# AdapterBoard.net
KiCad netlist of a schematic drawn in Altium Designer
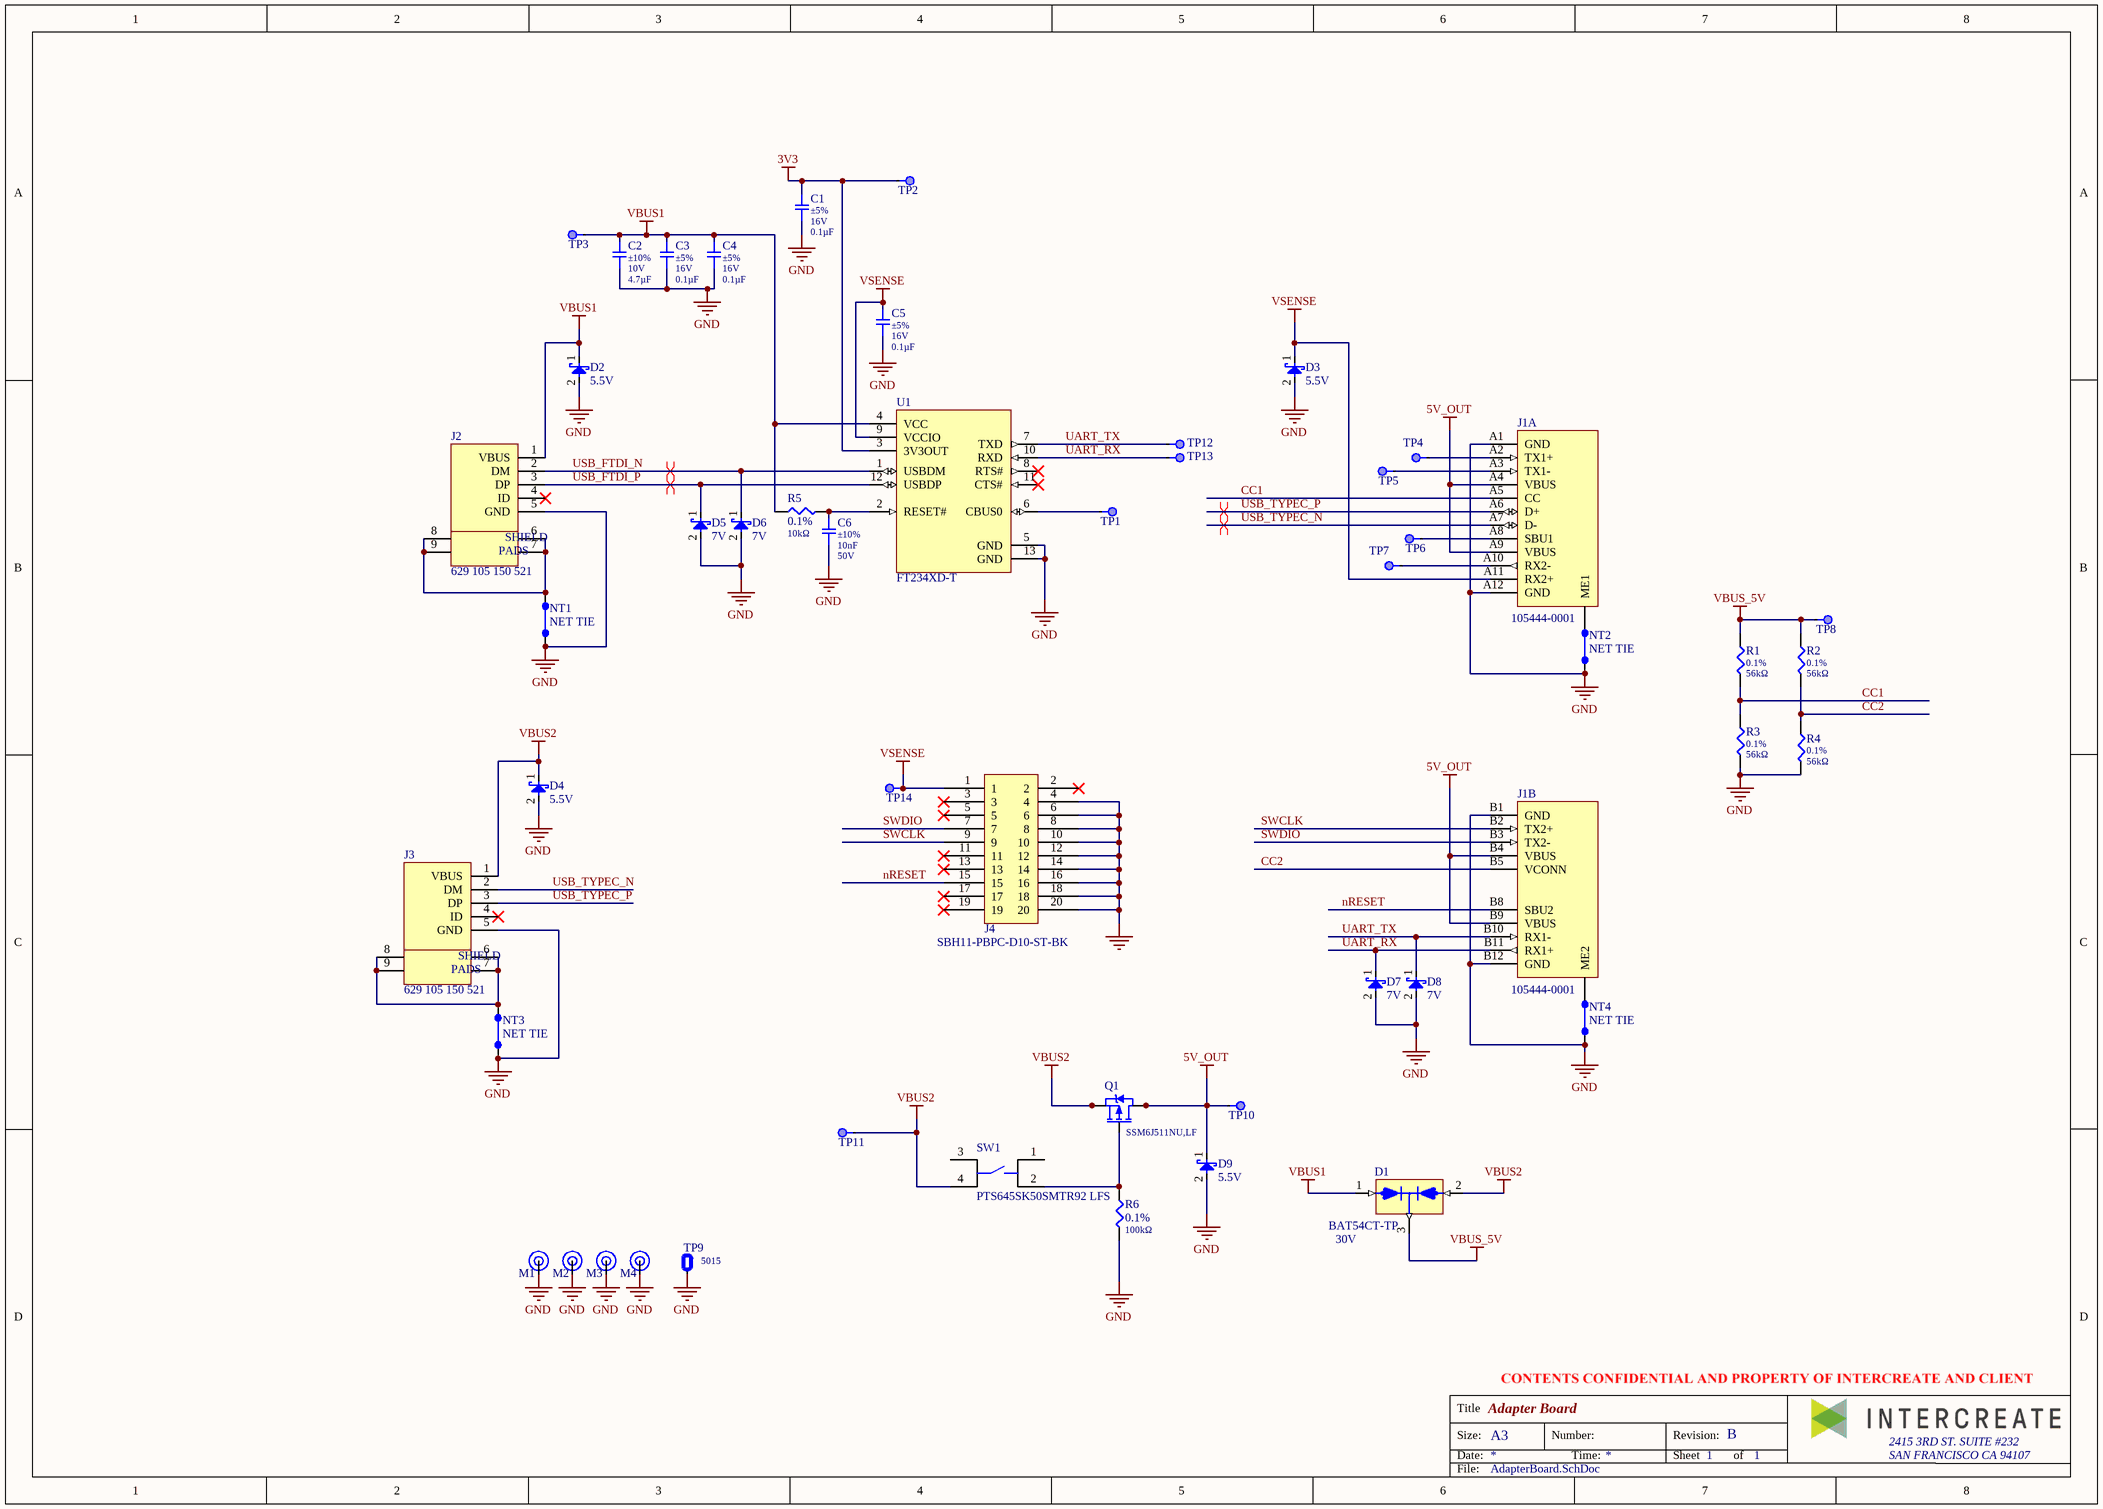
[diagram p0: AdapterBoard.SchDoc]

(export (version "E")
  (design (tool "Eeschema 10.0.6"))
  (components
    (comp (ref "C1")
      (value "0.1µF")
      (footprint "CAP-0402")
      (description "CAP CER 0.1UF 16V X7R 0402 5%")
      (fields
        (field (name "MANUFACTURER") "Murata")
        (field (name "MPN") "GRM155R71C104JA88D")
        (field (name "TOLERANCE") "±5%")
        (field (name "VOLTAGE RATING") "16V")
      )
      (libsource (lib "kagwerks") (part "CAP-0.1uF-16V-0402"))
    )
    (comp (ref "C2")
      (value "4.7µF")
      (footprint "CAP-0402")
      (description "CAP CER 4.7UF 10V X5R 0402 10%")
      (fields
        (field (name "MANUFACTURER") "Samsung")
        (field (name "MPN") "CL05A475KP5NRNC")
        (field (name "TOLERANCE") "±10%")
        (field (name "VOLTAGE RATING") "10V")
      )
      (libsource (lib "kagwerks") (part "CAP-4.7uF-10V-0402"))
    )
    (comp (ref "C3")
      (value "0.1µF")
      (footprint "CAP-0402")
      (description "CAP CER 0.1UF 16V X7R 0402 5%")
      (fields
        (field (name "MANUFACTURER") "Murata")
        (field (name "MPN") "GRM155R71C104JA88D")
        (field (name "TOLERANCE") "±5%")
        (field (name "VOLTAGE RATING") "16V")
      )
      (libsource (lib "kagwerks") (part "CAP-0.1uF-16V-0402"))
    )
    (comp (ref "C4")
      (value "0.1µF")
      (footprint "CAP-0402")
      (description "CAP CER 0.1UF 16V X7R 0402 5%")
      (fields
        (field (name "MANUFACTURER") "Murata")
        (field (name "MPN") "GRM155R71C104JA88D")
        (field (name "TOLERANCE") "±5%")
        (field (name "VOLTAGE RATING") "16V")
      )
      (libsource (lib "kagwerks") (part "CAP-0.1uF-16V-0402"))
    )
    (comp (ref "C5")
      (value "0.1µF")
      (footprint "CAP-0402")
      (description "CAP CER 0.1UF 16V X7R 0402 5%")
      (fields
        (field (name "MANUFACTURER") "Murata")
        (field (name "MPN") "GRM155R71C104JA88D")
        (field (name "TOLERANCE") "±5%")
        (field (name "VOLTAGE RATING") "16V")
      )
      (libsource (lib "kagwerks") (part "CAP-0.1uF-16V-0402"))
    )
    (comp (ref "C6")
      (value "10nF")
      (footprint "CAP-0402")
      (description "CAP CER 10nF 50V X7R 0402 10%")
      (fields
        (field (name "MANUFACTURER") "Murata")
        (field (name "MPN") "GCM155R71H103KA55D")
        (field (name "TOLERANCE") "±10%")
        (field (name "VOLTAGE RATING") "50V")
      )
      (libsource (lib "kagwerks") (part "CAP-10nF-50V-0402"))
    )
    (comp (ref "D1")
      (value "BAT54CT-TP")
      (footprint "IC-SOT-523")
      (description "DIODE ARRAY SCHOTTKY 30V SOT523")
      (fields (field (name "VOLTAGE RATING (DC)") "30V"))
      (libsource (lib "kagwerks") (part "DIODE-SCHOTTKY-30V-BAT54CT"))
    )
    (comp (ref "D2")
      (value "DF2S6P2CTC,L3F")
      (footprint "DIODE-CST2C")
      (description "TVS DIODE 5.5VWM CST2C")
      (fields (field (name "REVERSE STANDOFF VOLTAGE") "5.5V"))
      (libsource (lib "kagwerks") (part "DIODE-TVS-5.5V-CST2C"))
    )
    (comp (ref "D3")
      (value "DF2S6P2CTC,L3F")
      (footprint "DIODE-CST2C")
      (description "TVS DIODE 5.5VWM CST2C")
      (fields (field (name "REVERSE STANDOFF VOLTAGE") "5.5V"))
      (libsource (lib "kagwerks") (part "DIODE-TVS-5.5V-CST2C"))
    )
    (comp (ref "D4")
      (value "DF2S6P2CTC,L3F")
      (footprint "DIODE-CST2C")
      (description "TVS DIODE 5.5VWM CST2C")
      (fields (field (name "REVERSE STANDOFF VOLTAGE") "5.5V"))
      (libsource (lib "kagwerks") (part "DIODE-TVS-5.5V-CST2C"))
    )
    (comp (ref "D5")
      (value "RF2943-000")
      (footprint "DIODE-0402-LITTLEFUSE")
      (description "TVS DIODE 7V 9.2V 0402/2DFN")
      (fields (field (name "REVERSE STANDOFF VOLTAGE") "7V"))
      (libsource (lib "kagwerks") (part "DIODE-TVS-7V-0402"))
    )
    (comp (ref "D6")
      (value "RF2943-000")
      (footprint "DIODE-0402-LITTLEFUSE")
      (description "TVS DIODE 7V 9.2V 0402/2DFN")
      (fields (field (name "REVERSE STANDOFF VOLTAGE") "7V"))
      (libsource (lib "kagwerks") (part "DIODE-TVS-7V-0402"))
    )
    (comp (ref "D7")
      (value "RF2943-000")
      (footprint "DIODE-0402-LITTLEFUSE")
      (description "TVS DIODE 7V 9.2V 0402/2DFN")
      (fields (field (name "REVERSE STANDOFF VOLTAGE") "7V"))
      (libsource (lib "kagwerks") (part "DIODE-TVS-7V-0402"))
    )
    (comp (ref "D8")
      (value "RF2943-000")
      (footprint "DIODE-0402-LITTLEFUSE")
      (description "TVS DIODE 7V 9.2V 0402/2DFN")
      (fields (field (name "REVERSE STANDOFF VOLTAGE") "7V"))
      (libsource (lib "kagwerks") (part "DIODE-TVS-7V-0402"))
    )
    (comp (ref "D9")
      (value "DF2S6P2CTC,L3F")
      (footprint "DIODE-CST2C")
      (description "TVS DIODE 5.5VWM CST2C")
      (fields (field (name "REVERSE STANDOFF VOLTAGE") "5.5V"))
      (libsource (lib "kagwerks") (part "DIODE-TVS-5.5V-CST2C"))
    )
    (comp (ref "J1")
      (value "105444-0001")
      (footprint "CONN-M-USB-C")
      (description "105444-0001 Male USB C Connector, Right Angle Surface Mount")
      (libsource (lib "kagwerks") (part "CONN-M-USB-C"))
    )
    (comp (ref "J2")
      (value "629 105 150 521")
      (footprint "CONN-R-USB-UB-629105150521")
      (description "CONN RCPT USB MICRO B R/A")
      (libsource (lib "kagwerks") (part "CONN-R-USB-uB-WURTH"))
    )
    (comp (ref "J3")
      (value "629 105 150 521")
      (footprint "CONN-R-USB-UB-629105150521")
      (description "CONN RCPT USB MICRO B R/A")
      (libsource (lib "kagwerks") (part "CONN-R-USB-uB-WURTH"))
    )
    (comp (ref "J4")
      (value "SBH11-PBPC-D10-ST-BK")
      (footprint "HDR-V-2x10-KEYED")
      (description "CONN HEADER VERT 20POS 2.54MM")
      (libsource (lib "kagwerks") (part "HDR-V-2x10-M"))
    )
    (comp (ref "M1")
      (value "N/A")
      (footprint "HOLE-M2-NO-SILK")
      (description "MOUNTING HOLES, VARIOUS DIAMETERS")
      (libsource (lib "kagwerks") (part "HOLE"))
    )
    (comp (ref "M2")
      (value "N/A")
      (footprint "HOLE-M2-NO-SILK")
      (description "MOUNTING HOLES, VARIOUS DIAMETERS")
      (libsource (lib "kagwerks") (part "HOLE"))
    )
    (comp (ref "M3")
      (value "N/A")
      (footprint "HOLE-M2-NO-SILK")
      (description "MOUNTING HOLES, VARIOUS DIAMETERS")
      (libsource (lib "kagwerks") (part "HOLE"))
    )
    (comp (ref "M4")
      (value "N/A")
      (footprint "HOLE-M2-NO-SILK")
      (description "MOUNTING HOLES, VARIOUS DIAMETERS")
      (libsource (lib "kagwerks") (part "HOLE"))
    )
    (comp (ref "NT1") (value "NET TIE") (footprint "NET_TIE") (libsource (lib "kagwerks") (part "NET TIE")))
    (comp (ref "NT2") (value "NET TIE") (footprint "NET_TIE") (libsource (lib "kagwerks") (part "NET TIE")))
    (comp (ref "NT3") (value "NET TIE") (footprint "NET_TIE") (libsource (lib "kagwerks") (part "NET TIE")))
    (comp (ref "NT4") (value "NET TIE") (footprint "NET_TIE") (libsource (lib "kagwerks") (part "NET TIE")))
    (comp (ref "Q1")
      (value "SSM6J511NU,LF")
      (footprint "FET-6-DFN-EP")
      (description "MOSFET P-CH 12V 14A UDFN6B")
      (fields (field (name "MANUFACTURER") "Toshiba"))
      (libsource (lib "kagwerks") (part "PMOS-12V-14A-UDFN6"))
    )
    (comp (ref "R1")
      (value "56kΩ")
      (footprint "RES-0402")
      (description "RES SMD 56K OHM 0.1% 1/16W 0402")
      (fields (field (name "TOLERANCE") "0.1%") (field (name "Comment") "RT0402BRD0756KL"))
      (libsource (lib "kagwerks") (part "RES-56K-0402-0.1%"))
    )
    (comp (ref "R2")
      (value "56kΩ")
      (footprint "RES-0402")
      (description "RES SMD 56K OHM 0.1% 1/16W 0402")
      (fields (field (name "TOLERANCE") "0.1%") (field (name "Comment") "RT0402BRD0756KL"))
      (libsource (lib "kagwerks") (part "RES-56K-0402-0.1%"))
    )
    (comp (ref "R3")
      (value "56kΩ")
      (footprint "RES-0402")
      (description "RES SMD 56K OHM 0.1% 1/16W 0402")
      (fields (field (name "TOLERANCE") "0.1%") (field (name "Comment") "RT0402BRD0756KL"))
      (libsource (lib "kagwerks") (part "RES-56K-0402-0.1%"))
    )
    (comp (ref "R4")
      (value "56kΩ")
      (footprint "RES-0402")
      (description "RES SMD 56K OHM 0.1% 1/16W 0402")
      (fields (field (name "TOLERANCE") "0.1%") (field (name "Comment") "RT0402BRD0756KL"))
      (libsource (lib "kagwerks") (part "RES-56K-0402-0.1%"))
    )
    (comp (ref "R5")
      (value "10kΩ")
      (footprint "RES-0402")
      (description "RES SMD 10K OHM 0.1% 1/16W 0402")
      (fields (field (name "TOLERANCE") "0.1%") (field (name "Comment") "RT0402BRE0710KL"))
      (libsource (lib "kagwerks") (part "RES-10K-0402-0.1%"))
    )
    (comp (ref "R6")
      (value "100kΩ")
      (footprint "RES-0402")
      (description "RES SMD 100KOHM 0.1% 1/16W 0402")
      (fields (field (name "TOLERANCE") "0.1%") (field (name "Comment") "RT0402BRD07100KL"))
      (libsource (lib "kagwerks") (part "RES-100K-0402-0.1%"))
    )
    (comp (ref "SW1")
      (value "PTS645SK50SMTR92 LFS")
      (footprint "BTN-SPST-PTS645SK50SMTR92")
      (description "C & K COMPONENTS - PTS645SK50SMTR92LFS - SWITCH, SPST, 0.05A, 12VDC, SMD, 5MM")
      (libsource (lib "intercreate") (part "BTN-SPST-PTS645SK50SMTR92"))
    )
    (comp (ref "TP1")
      (value "N/A")
      (footprint "TP-0.75MM")
      (description "TESTPOINT - VARIOUS SHAPES")
      (libsource (lib "kagwerks") (part "TP"))
    )
    (comp (ref "TP2")
      (value "N/A")
      (footprint "TP-0.75MM")
      (description "TESTPOINT - VARIOUS SHAPES")
      (libsource (lib "kagwerks") (part "TP"))
    )
    (comp (ref "TP3")
      (value "N/A")
      (footprint "TP-0.75MM")
      (description "TESTPOINT - VARIOUS SHAPES")
      (libsource (lib "kagwerks") (part "TP"))
    )
    (comp (ref "TP4")
      (value "N/A")
      (footprint "TP-0.75MM")
      (description "TESTPOINT - VARIOUS SHAPES")
      (libsource (lib "kagwerks") (part "TP"))
    )
    (comp (ref "TP5")
      (value "N/A")
      (footprint "TP-0.75MM")
      (description "TESTPOINT - VARIOUS SHAPES")
      (libsource (lib "kagwerks") (part "TP"))
    )
    (comp (ref "TP6")
      (value "N/A")
      (footprint "TP-0.75MM")
      (description "TESTPOINT - VARIOUS SHAPES")
      (libsource (lib "kagwerks") (part "TP"))
    )
    (comp (ref "TP7")
      (value "N/A")
      (footprint "TP-0.75MM")
      (description "TESTPOINT - VARIOUS SHAPES")
      (libsource (lib "kagwerks") (part "TP"))
    )
    (comp (ref "TP8")
      (value "N/A")
      (footprint "TP-0.75MM")
      (description "TESTPOINT - VARIOUS SHAPES")
      (libsource (lib "kagwerks") (part "TP"))
    )
    (comp (ref "TP9")
      (value "5015")
      (footprint "TP-5015")
      (description "PC TEST POINT MINIATURE")
      (libsource (lib "kagwerks") (part "TP-5015"))
    )
    (comp (ref "TP10")
      (value "N/A")
      (footprint "TP-0.75MM")
      (description "TESTPOINT - VARIOUS SHAPES")
      (libsource (lib "kagwerks") (part "TP"))
    )
    (comp (ref "TP11")
      (value "N/A")
      (footprint "TP-0.75MM")
      (description "TESTPOINT - VARIOUS SHAPES")
      (libsource (lib "kagwerks") (part "TP"))
    )
    (comp (ref "TP12")
      (value "N/A")
      (footprint "TP-0.75MM")
      (description "TESTPOINT - VARIOUS SHAPES")
      (libsource (lib "kagwerks") (part "TP"))
    )
    (comp (ref "TP13")
      (value "N/A")
      (footprint "TP-0.75MM")
      (description "TESTPOINT - VARIOUS SHAPES")
      (libsource (lib "kagwerks") (part "TP"))
    )
    (comp (ref "TP14")
      (value "N/A")
      (footprint "TP-0.75MM")
      (description "TESTPOINT - VARIOUS SHAPES")
      (libsource (lib "kagwerks") (part "TP"))
    )
    (comp (ref "U1")
      (value "FT234XD-T")
      (footprint "IC-DFN-12P")
      (description "USB Full Speed to Basic UART IC with USB Charger Detection")
      (libsource (lib "kagwerks") (part "IC-USB-FTDI-FT234XD"))
    )
  )
  (nets
    (net (code "1") (name "/CC1") (class "Default")
      (node (ref "J1") (pin "A5") (pinfunction "CC_A5") (pintype "power_in"))
      (node (ref "R1") (pin "2") (pinfunction "2_2") (pintype "passive"))
      (node (ref "R3") (pin "1") (pinfunction "1_1") (pintype "passive"))
    )
    (net (code "2") (name "/CC2") (class "Default")
      (node (ref "J1") (pin "B5") (pinfunction "VCONN_B5") (pintype "power_in"))
      (node (ref "R2") (pin "2") (pinfunction "2_2") (pintype "passive"))
      (node (ref "R4") (pin "1") (pinfunction "1_1") (pintype "passive"))
    )
    (net (code "3") (name "/SWCLK") (class "Default")
      (node (ref "J1") (pin "B2") (pinfunction "TX2+_B2") (pintype "input"))
      (node (ref "J4") (pin "9") (pinfunction "9_9") (pintype "passive"))
    )
    (net (code "4") (name "/SWDIO") (class "Default")
      (node (ref "J1") (pin "B3") (pinfunction "TX2-_B3") (pintype "input"))
      (node (ref "J4") (pin "7") (pinfunction "7_7") (pintype "passive"))
    )
    (net (code "5") (name "/UART_RX") (class "Default")
      (node (ref "D7") (pin "1") (pinfunction "K_1") (pintype "passive"))
      (node (ref "J1") (pin "B11") (pinfunction "RX1+_B11") (pintype "output"))
      (node (ref "TP13") (pin "1") (pinfunction "TP_1P0MM_1") (pintype "passive"))
      (node (ref "U1") (pin "10") (pinfunction "RXD_10") (pintype "input"))
    )
    (net (code "6") (name "/UART_TX") (class "Default")
      (node (ref "D8") (pin "1") (pinfunction "K_1") (pintype "passive"))
      (node (ref "J1") (pin "B10") (pinfunction "RX1-_B10") (pintype "input"))
      (node (ref "TP12") (pin "1") (pinfunction "TP_1P0MM_1") (pintype "passive"))
      (node (ref "U1") (pin "7") (pinfunction "TXD_7") (pintype "output"))
    )
    (net (code "7") (name "/USB_FTDI_N") (class "Default")
      (node (ref "D6") (pin "1") (pinfunction "K_1") (pintype "passive"))
      (node (ref "J2") (pin "2") (pinfunction "DM_2") (pintype "passive"))
      (node (ref "U1") (pin "1") (pinfunction "USBDM_1") (pintype "bidirectional"))
    )
    (net (code "8") (name "/USB_FTDI_P") (class "Default")
      (node (ref "D5") (pin "1") (pinfunction "K_1") (pintype "passive"))
      (node (ref "J2") (pin "3") (pinfunction "DP_3") (pintype "passive"))
      (node (ref "U1") (pin "12") (pinfunction "USBDP_12") (pintype "bidirectional"))
    )
    (net (code "9") (name "/USB_TYPEC_N") (class "Default")
      (node (ref "J1") (pin "A7") (pinfunction "D-_A7") (pintype "bidirectional"))
      (node (ref "J3") (pin "2") (pinfunction "DM_2") (pintype "passive"))
    )
    (net (code "10") (name "/USB_TYPEC_P") (class "Default")
      (node (ref "J1") (pin "A6") (pinfunction "D+_A6") (pintype "bidirectional"))
      (node (ref "J3") (pin "3") (pinfunction "DP_3") (pintype "passive"))
    )
    (net (code "11") (name "/nRESET") (class "Default")
      (node (ref "J1") (pin "B8") (pinfunction "SBU2_B8") (pintype "power_in"))
      (node (ref "J4") (pin "15") (pinfunction "15_15") (pintype "power_in"))
    )
    (net (code "12") (name "3V3") (class "Default")
      (node (ref "C1") (pin "2") (pinfunction "2_2") (pintype "passive"))
      (node (ref "TP2") (pin "1") (pinfunction "TP_1P0MM_1") (pintype "passive"))
      (node (ref "U1") (pin "3") (pinfunction "3V3OUT_3") (pintype "power_in"))
    )
    (net (code "13") (name "5V_OUT") (class "Default")
      (node (ref "D9") (pin "1") (pinfunction "K_1") (pintype "passive"))
      (node (ref "J1") (pin "A4") (pinfunction "VBUS_A4") (pintype "power_in"))
      (node (ref "J1") (pin "A9") (pinfunction "VBUS_A9") (pintype "power_in"))
      (node (ref "J1") (pin "B4") (pinfunction "VBUS_B4") (pintype "power_in"))
      (node (ref "J1") (pin "B9") (pinfunction "VBUS_B9") (pintype "power_in"))
      (node (ref "Q1") (pin "1") (pinfunction "D_1") (pintype "passive"))
      (node (ref "Q1") (pin "2") (pinfunction "D_2") (pintype "passive"))
      (node (ref "Q1") (pin "5") (pinfunction "D_5") (pintype "passive"))
      (node (ref "Q1") (pin "6") (pinfunction "D_6") (pintype "passive"))
      (node (ref "Q1") (pin "8") (pinfunction "D_8") (pintype "passive"))
      (node (ref "TP10") (pin "1") (pinfunction "TP_1P0MM_1") (pintype "passive"))
    )
    (net (code "14") (name "GND") (class "Default")
      (node (ref "C1") (pin "1") (pinfunction "1_1") (pintype "passive"))
      (node (ref "C2") (pin "1") (pinfunction "1_1") (pintype "passive"))
      (node (ref "C3") (pin "1") (pinfunction "1_1") (pintype "passive"))
      (node (ref "C4") (pin "1") (pinfunction "1_1") (pintype "passive"))
      (node (ref "C5") (pin "1") (pinfunction "1_1") (pintype "passive"))
      (node (ref "C6") (pin "1") (pinfunction "1_1") (pintype "passive"))
      (node (ref "D2") (pin "2") (pinfunction "A_2") (pintype "passive"))
      (node (ref "D3") (pin "2") (pinfunction "A_2") (pintype "passive"))
      (node (ref "D4") (pin "2") (pinfunction "A_2") (pintype "passive"))
      (node (ref "D5") (pin "2") (pinfunction "A_2") (pintype "passive"))
      (node (ref "D6") (pin "2") (pinfunction "A_2") (pintype "passive"))
      (node (ref "D7") (pin "2") (pinfunction "A_2") (pintype "passive"))
      (node (ref "D8") (pin "2") (pinfunction "A_2") (pintype "passive"))
      (node (ref "D9") (pin "2") (pinfunction "A_2") (pintype "passive"))
      (node (ref "J1") (pin "A1") (pinfunction "GND_A1") (pintype "power_in"))
      (node (ref "J1") (pin "A12") (pinfunction "GND_A12") (pintype "power_in"))
      (node (ref "J1") (pin "B1") (pinfunction "GND_B1") (pintype "power_in"))
      (node (ref "J1") (pin "B12") (pinfunction "GND_B12") (pintype "power_in"))
      (node (ref "J2") (pin "5") (pinfunction "GND_5") (pintype "passive"))
      (node (ref "J3") (pin "5") (pinfunction "GND_5") (pintype "passive"))
      (node (ref "J4") (pin "10") (pinfunction "10_10") (pintype "passive"))
      (node (ref "J4") (pin "12") (pinfunction "12_12") (pintype "power_in"))
      (node (ref "J4") (pin "14") (pinfunction "14_14") (pintype "power_in"))
      (node (ref "J4") (pin "16") (pinfunction "16_16") (pintype "power_in"))
      (node (ref "J4") (pin "18") (pinfunction "18_18") (pintype "power_in"))
      (node (ref "J4") (pin "20") (pinfunction "20_20") (pintype "power_in"))
      (node (ref "J4") (pin "4") (pinfunction "4_4") (pintype "passive"))
      (node (ref "J4") (pin "6") (pinfunction "6_6") (pintype "passive"))
      (node (ref "J4") (pin "8") (pinfunction "8_8") (pintype "passive"))
      (node (ref "M1") (pin "1") (pinfunction "1_1") (pintype "passive"))
      (node (ref "M2") (pin "1") (pinfunction "1_1") (pintype "passive"))
      (node (ref "M3") (pin "1") (pinfunction "1_1") (pintype "passive"))
      (node (ref "M4") (pin "1") (pinfunction "1_1") (pintype "passive"))
      (node (ref "NT1") (pin "1") (pinfunction "1_1") (pintype "passive"))
      (node (ref "NT2") (pin "1") (pinfunction "1_1") (pintype "passive"))
      (node (ref "NT3") (pin "1") (pinfunction "1_1") (pintype "passive"))
      (node (ref "NT4") (pin "1") (pinfunction "1_1") (pintype "passive"))
      (node (ref "R3") (pin "2") (pinfunction "2_2") (pintype "passive"))
      (node (ref "R4") (pin "2") (pinfunction "2_2") (pintype "passive"))
      (node (ref "R6") (pin "2") (pinfunction "2_2") (pintype "passive"))
      (node (ref "TP9") (pin "1") (pinfunction "1_1") (pintype "passive"))
      (node (ref "U1") (pin "13") (pinfunction "GND_13") (pintype "power_in"))
      (node (ref "U1") (pin "5") (pinfunction "GND_5") (pintype "power_in"))
    )
    (net (code "15") (name "Net-(J1-PadME1)") (class "Default")
      (node (ref "J1") (pin "ME1") (pinfunction "ME1_ME1") (pintype "power_in"))
      (node (ref "NT2") (pin "2") (pinfunction "2_2") (pintype "passive"))
    )
    (net (code "16") (name "Net-(J1-PadME2)") (class "Default")
      (node (ref "J1") (pin "ME2") (pinfunction "ME2_ME2") (pintype "power_in"))
      (node (ref "NT4") (pin "2") (pinfunction "2_2") (pintype "passive"))
    )
    (net (code "17") (name "Net-(J1A-RX2-)") (class "Default")
      (node (ref "J1") (pin "A10") (pinfunction "RX2-_A10") (pintype "output"))
      (node (ref "TP7") (pin "1") (pinfunction "TP_1P0MM_1") (pintype "passive"))
    )
    (net (code "18") (name "Net-(J1A-SBU1)") (class "Default")
      (node (ref "J1") (pin "A8") (pinfunction "SBU1_A8") (pintype "power_in"))
      (node (ref "TP6") (pin "1") (pinfunction "TP_1P0MM_1") (pintype "passive"))
    )
    (net (code "19") (name "Net-(J1A-TX1+)") (class "Default")
      (node (ref "J1") (pin "A2") (pinfunction "TX1+_A2") (pintype "input"))
      (node (ref "TP4") (pin "1") (pinfunction "TP_1P0MM_1") (pintype "passive"))
    )
    (net (code "20") (name "Net-(J1A-TX1-)") (class "Default")
      (node (ref "J1") (pin "A3") (pinfunction "TX1-_A3") (pintype "input"))
      (node (ref "TP5") (pin "1") (pinfunction "TP_1P0MM_1") (pintype "passive"))
    )
    (net (code "21") (name "Net-(J2-PAD-Pad6)") (class "Default")
      (node (ref "J2") (pin "6") (pinfunction "PAD_6") (pintype "passive"))
      (node (ref "J2") (pin "7") (pinfunction "PAD_7") (pintype "passive"))
      (node (ref "J2") (pin "8") (pinfunction "PAD_8") (pintype "passive"))
      (node (ref "J2") (pin "9") (pinfunction "PAD_9") (pintype "passive"))
      (node (ref "NT1") (pin "2") (pinfunction "2_2") (pintype "passive"))
    )
    (net (code "22") (name "Net-(J3-PAD-Pad6)") (class "Default")
      (node (ref "J3") (pin "6") (pinfunction "PAD_6") (pintype "passive"))
      (node (ref "J3") (pin "7") (pinfunction "PAD_7") (pintype "passive"))
      (node (ref "J3") (pin "8") (pinfunction "PAD_8") (pintype "passive"))
      (node (ref "J3") (pin "9") (pinfunction "PAD_9") (pintype "passive"))
      (node (ref "NT3") (pin "2") (pinfunction "2_2") (pintype "passive"))
    )
    (net (code "23") (name "Net-(Q1-G)") (class "Default")
      (node (ref "Q1") (pin "3") (pinfunction "G_3") (pintype "passive"))
      (node (ref "R6") (pin "1") (pinfunction "1_1") (pintype "passive"))
      (node (ref "SW1") (pin "2") (pinfunction "2_2") (pintype "passive"))
    )
    (net (code "24") (name "Net-(TP1-TP_1P0MM)") (class "Default")
      (node (ref "TP1") (pin "1") (pinfunction "TP_1P0MM_1") (pintype "passive"))
      (node (ref "U1") (pin "6") (pinfunction "CBUS0_6") (pintype "bidirectional"))
    )
    (net (code "25") (name "Net-(U1-RESET#)") (class "Default")
      (node (ref "C6") (pin "2") (pinfunction "2_2") (pintype "passive"))
      (node (ref "R5") (pin "2") (pinfunction "2_2") (pintype "passive"))
      (node (ref "U1") (pin "2") (pinfunction "RESET#_2") (pintype "input"))
    )
    (net (code "26") (name "VBUS1") (class "Default")
      (node (ref "C2") (pin "2") (pinfunction "2_2") (pintype "passive"))
      (node (ref "C3") (pin "2") (pinfunction "2_2") (pintype "passive"))
      (node (ref "C4") (pin "2") (pinfunction "2_2") (pintype "passive"))
      (node (ref "D1") (pin "1") (pinfunction "1_1") (pintype "input"))
      (node (ref "D2") (pin "1") (pinfunction "K_1") (pintype "passive"))
      (node (ref "J2") (pin "1") (pinfunction "VBUS_1") (pintype "passive"))
      (node (ref "R5") (pin "1") (pinfunction "1_1") (pintype "passive"))
      (node (ref "TP3") (pin "1") (pinfunction "TP_1P0MM_1") (pintype "passive"))
      (node (ref "U1") (pin "4") (pinfunction "VCC_4") (pintype "power_in"))
    )
    (net (code "27") (name "VBUS2") (class "Default")
      (node (ref "D1") (pin "2") (pinfunction "2_2") (pintype "input"))
      (node (ref "D4") (pin "1") (pinfunction "K_1") (pintype "passive"))
      (node (ref "J3") (pin "1") (pinfunction "VBUS_1") (pintype "passive"))
      (node (ref "Q1") (pin "4") (pinfunction "S_4") (pintype "passive"))
      (node (ref "Q1") (pin "7") (pinfunction "S_7") (pintype "passive"))
      (node (ref "SW1") (pin "4") (pinfunction "4_4") (pintype "passive"))
      (node (ref "TP11") (pin "1") (pinfunction "TP_1P0MM_1") (pintype "passive"))
    )
    (net (code "28") (name "VBUS_5V") (class "Default")
      (node (ref "D1") (pin "3") (pinfunction "3_3") (pintype "output"))
      (node (ref "R1") (pin "1") (pinfunction "1_1") (pintype "passive"))
      (node (ref "R2") (pin "1") (pinfunction "1_1") (pintype "passive"))
      (node (ref "TP8") (pin "1") (pinfunction "TP_1P0MM_1") (pintype "passive"))
    )
    (net (code "29") (name "VSENSE") (class "Default")
      (node (ref "C5") (pin "2") (pinfunction "2_2") (pintype "passive"))
      (node (ref "D3") (pin "1") (pinfunction "K_1") (pintype "passive"))
      (node (ref "J1") (pin "A11") (pinfunction "RX2+_A11") (pintype "output"))
      (node (ref "J4") (pin "1") (pinfunction "1_1") (pintype "passive"))
      (node (ref "TP14") (pin "1") (pinfunction "TP_1P0MM_1") (pintype "passive"))
      (node (ref "U1") (pin "9") (pinfunction "VCCIO_9") (pintype "power_in"))
    )
    (net (code "30") (name "unconnected-(J2-ID-Pad4)") (class "Default")
      (node (ref "J2") (pin "4") (pinfunction "ID_4") (pintype "passive+no_connect"))
    )
    (net (code "31") (name "unconnected-(J3-ID-Pad4)") (class "Default")
      (node (ref "J3") (pin "4") (pinfunction "ID_4") (pintype "passive+no_connect"))
    )
    (net (code "32") (name "unconnected-(J4-Pad2)") (class "Default")
      (node (ref "J4") (pin "2") (pinfunction "2_2") (pintype "passive+no_connect"))
    )
    (net (code "33") (name "unconnected-(J4-Pad3)") (class "Default")
      (node (ref "J4") (pin "3") (pinfunction "3_3") (pintype "passive+no_connect"))
    )
    (net (code "34") (name "unconnected-(J4-Pad5)") (class "Default")
      (node (ref "J4") (pin "5") (pinfunction "5_5") (pintype "passive+no_connect"))
    )
    (net (code "35") (name "unconnected-(J4-Pad11)") (class "Default")
      (node (ref "J4") (pin "11") (pinfunction "11_11") (pintype "power_in+no_connect"))
    )
    (net (code "36") (name "unconnected-(J4-Pad13)") (class "Default")
      (node (ref "J4") (pin "13") (pinfunction "13_13") (pintype "power_in+no_connect"))
    )
    (net (code "37") (name "unconnected-(J4-Pad17)") (class "Default")
      (node (ref "J4") (pin "17") (pinfunction "17_17") (pintype "power_in+no_connect"))
    )
    (net (code "38") (name "unconnected-(J4-Pad19)") (class "Default")
      (node (ref "J4") (pin "19") (pinfunction "19_19") (pintype "power_in+no_connect"))
    )
    (net (code "39") (name "unconnected-(SW1-Pad1)") (class "Default")
      (node (ref "SW1") (pin "1") (pinfunction "1_1") (pintype "passive"))
    )
    (net (code "40") (name "unconnected-(SW1-Pad3)") (class "Default")
      (node (ref "SW1") (pin "3") (pinfunction "3_3") (pintype "passive"))
    )
    (net (code "41") (name "unconnected-(U1-CTS#-Pad11)") (class "Default")
      (node (ref "U1") (pin "11") (pinfunction "CTS#_11") (pintype "input+no_connect"))
    )
    (net (code "42") (name "unconnected-(U1-RTS#-Pad8)") (class "Default")
      (node (ref "U1") (pin "8") (pinfunction "RTS#_8") (pintype "output+no_connect"))
    )
  )
)
